# Stepper_Driver.net
KiCad netlist of a schematic drawn in EAGLE
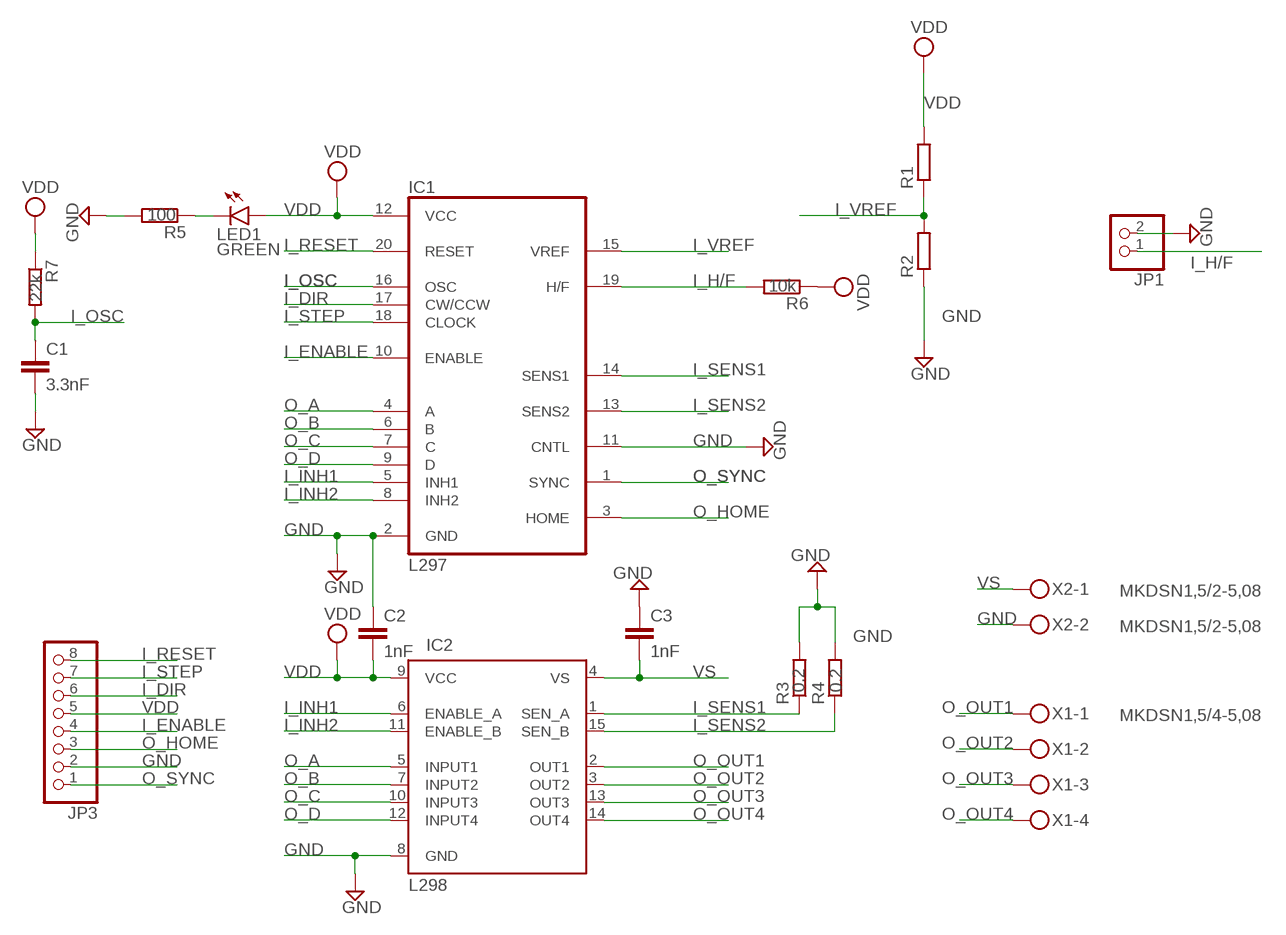
[diagram p0: schematic, sheet 1]

(export (version "E")
  (design (tool "Eeschema 10.0.6"))
  (components
    (comp (ref "C1")
      (value "3.3nF")
      (footprint "eagle-import:C0805K")
      (libsource (lib "eagle-import") (part "C-EUC0805K"))
    )
    (comp (ref "C2")
      (value "1nF")
      (footprint "eagle-import:C0805K")
      (libsource (lib "eagle-import") (part "C-EUC0805K"))
    )
    (comp (ref "C3")
      (value "1nF")
      (footprint "eagle-import:C0805K")
      (libsource (lib "eagle-import") (part "C-EUC0805K"))
    )
    (comp (ref "IC1")
      (value "L297")
      (footprint "eagle-import:DIL20")
      (fields (field (name "MPN") "L297/1"))
      (libsource (lib "eagle-import") (part "L297"))
    )
    (comp (ref "IC2")
      (value "L298")
      (footprint "eagle-import:MULTIWATT-15")
      (fields (field (name "MPN") "L298N"))
      (libsource (lib "eagle-import") (part "L298"))
    )
    (comp (ref "JP1")
      (value "PINHD-1X2")
      (footprint "eagle-import:1X02")
      (libsource (lib "eagle-import") (part "PINHD-1X2"))
    )
    (comp (ref "JP3")
      (value "PINHD-1X8")
      (footprint "eagle-import:1X08")
      (libsource (lib "eagle-import") (part "PINHD-1X8"))
    )
    (comp (ref "LED1")
      (value "GREEN")
      (footprint "eagle-import:LED5MM")
      (libsource (lib "eagle-import") (part "LED5MM"))
    )
    (comp (ref "R1")
      (value "R-EU_R0805")
      (footprint "eagle-import:R0805")
      (libsource (lib "eagle-import") (part "R-EU_R0805"))
    )
    (comp (ref "R2")
      (value "R-EU_R0805")
      (footprint "eagle-import:R0805")
      (libsource (lib "eagle-import") (part "R-EU_R0805"))
    )
    (comp (ref "R3")
      (value "0.2")
      (footprint "eagle-import:R2512")
      (libsource (lib "eagle-import") (part "R-EU_R2512"))
    )
    (comp (ref "R4")
      (value "0.2")
      (footprint "eagle-import:R2512")
      (libsource (lib "eagle-import") (part "R-EU_R2512"))
    )
    (comp (ref "R5")
      (value "100")
      (footprint "eagle-import:R0805")
      (libsource (lib "eagle-import") (part "R-EU_R0805"))
    )
    (comp (ref "R6")
      (value "10k")
      (footprint "eagle-import:R0805")
      (libsource (lib "eagle-import") (part "R-EU_R0805"))
    )
    (comp (ref "R7")
      (value "22k")
      (footprint "eagle-import:R0805")
      (libsource (lib "eagle-import") (part "R-EU_R0805"))
    )
    (comp (ref "X1")
      (value "MKDSN1,5/4-5,08")
      (footprint "eagle-import:MKDSN1,5_4-5,08")
      (libsource (lib "eagle-import") (part "MKDSN1,5/4-5,08"))
    )
    (comp (ref "X2")
      (value "MKDSN1,5/2-5,08")
      (footprint "eagle-import:MKDSN1,5_2-5,08")
      (libsource (lib "eagle-import") (part "MKDSN1,5/2-5,08"))
    )
  )
  (nets
    (net (code "1") (name "/I_DIR") (class "Default")
      (node (ref "IC1") (pin "17") (pinfunction "CW/CCW_17") (pintype "input"))
      (node (ref "JP3") (pin "6") (pinfunction "6_6") (pintype "passive"))
    )
    (net (code "2") (name "/I_ENABLE") (class "Default")
      (node (ref "IC1") (pin "10") (pinfunction "ENABLE_10") (pintype "input"))
      (node (ref "JP3") (pin "4") (pinfunction "4_4") (pintype "passive"))
    )
    (net (code "3") (name "/I_H{slash}F") (class "Default")
      (node (ref "IC1") (pin "19") (pinfunction "H/F_19") (pintype "input"))
      (node (ref "JP1") (pin "1") (pinfunction "1_1") (pintype "passive"))
      (node (ref "R6") (pin "2") (pinfunction "2_2") (pintype "passive"))
    )
    (net (code "4") (name "/I_INH1") (class "Default")
      (node (ref "IC1") (pin "5") (pinfunction "INH1_5") (pintype "output"))
      (node (ref "IC2") (pin "6") (pinfunction "ENABLE_A_6") (pintype "input"))
    )
    (net (code "5") (name "/I_INH2") (class "Default")
      (node (ref "IC1") (pin "8") (pinfunction "INH2_8") (pintype "output"))
      (node (ref "IC2") (pin "11") (pinfunction "ENABLE_B_11") (pintype "input"))
    )
    (net (code "6") (name "/I_OSC") (class "Default")
      (node (ref "C1") (pin "1") (pinfunction "1_1") (pintype "passive"))
      (node (ref "IC1") (pin "16") (pinfunction "OSC_16") (pintype "bidirectional"))
      (node (ref "R7") (pin "2") (pinfunction "2_2") (pintype "passive"))
    )
    (net (code "7") (name "/I_RESET") (class "Default")
      (node (ref "IC1") (pin "20") (pinfunction "RESET_20") (pintype "input"))
      (node (ref "JP3") (pin "8") (pinfunction "8_8") (pintype "passive"))
    )
    (net (code "8") (name "/I_SENS1") (class "Default")
      (node (ref "IC1") (pin "14") (pinfunction "SENS1_14") (pintype "output"))
      (node (ref "IC2") (pin "1") (pinfunction "SEN_A_1") (pintype "input"))
      (node (ref "R3") (pin "1") (pinfunction "1_1") (pintype "passive"))
    )
    (net (code "9") (name "/I_SENS2") (class "Default")
      (node (ref "IC1") (pin "13") (pinfunction "SENS2_13") (pintype "output"))
      (node (ref "IC2") (pin "15") (pinfunction "SEN_B_15") (pintype "input"))
      (node (ref "R4") (pin "1") (pinfunction "1_1") (pintype "passive"))
    )
    (net (code "10") (name "/I_STEP") (class "Default")
      (node (ref "IC1") (pin "18") (pinfunction "CLOCK_18") (pintype "input"))
      (node (ref "JP3") (pin "7") (pinfunction "7_7") (pintype "passive"))
    )
    (net (code "11") (name "/I_VREF") (class "Default")
      (node (ref "IC1") (pin "15") (pinfunction "VREF_15") (pintype "input"))
      (node (ref "R1") (pin "1") (pinfunction "1_1") (pintype "passive"))
      (node (ref "R2") (pin "2") (pinfunction "2_2") (pintype "passive"))
    )
    (net (code "12") (name "/O_A") (class "Default")
      (node (ref "IC1") (pin "4") (pinfunction "A_4") (pintype "output"))
      (node (ref "IC2") (pin "5") (pinfunction "INPUT1_5") (pintype "input"))
    )
    (net (code "13") (name "/O_B") (class "Default")
      (node (ref "IC1") (pin "6") (pinfunction "B_6") (pintype "output"))
      (node (ref "IC2") (pin "7") (pinfunction "INPUT2_7") (pintype "input"))
    )
    (net (code "14") (name "/O_C") (class "Default")
      (node (ref "IC1") (pin "7") (pinfunction "C_7") (pintype "output"))
      (node (ref "IC2") (pin "10") (pinfunction "INPUT3_10") (pintype "input"))
    )
    (net (code "15") (name "/O_D") (class "Default")
      (node (ref "IC1") (pin "9") (pinfunction "D_9") (pintype "output"))
      (node (ref "IC2") (pin "12") (pinfunction "INPUT4_12") (pintype "input"))
    )
    (net (code "16") (name "/O_HOME") (class "Default")
      (node (ref "IC1") (pin "3") (pinfunction "HOME_3") (pintype "output"))
      (node (ref "JP3") (pin "3") (pinfunction "3_3") (pintype "passive"))
    )
    (net (code "17") (name "/O_OUT1") (class "Default")
      (node (ref "IC2") (pin "2") (pinfunction "OUT1_2") (pintype "output"))
      (node (ref "X1") (pin "1") (pinfunction "KL_1") (pintype "passive"))
    )
    (net (code "18") (name "/O_OUT2") (class "Default")
      (node (ref "IC2") (pin "3") (pinfunction "OUT2_3") (pintype "output"))
      (node (ref "X1") (pin "2") (pinfunction "KL_2") (pintype "passive"))
    )
    (net (code "19") (name "/O_OUT3") (class "Default")
      (node (ref "IC2") (pin "13") (pinfunction "OUT3_13") (pintype "output"))
      (node (ref "X1") (pin "3") (pinfunction "KL_3") (pintype "passive"))
    )
    (net (code "20") (name "/O_OUT4") (class "Default")
      (node (ref "IC2") (pin "14") (pinfunction "OUT4_14") (pintype "output"))
      (node (ref "X1") (pin "4") (pinfunction "KL_4") (pintype "passive"))
    )
    (net (code "21") (name "/O_SYNC") (class "Default")
      (node (ref "IC1") (pin "1") (pinfunction "SYNC_1") (pintype "output"))
      (node (ref "JP3") (pin "1") (pinfunction "1_1") (pintype "passive"))
    )
    (net (code "22") (name "/VS") (class "Default")
      (node (ref "C3") (pin "2") (pinfunction "2_2") (pintype "passive"))
      (node (ref "IC2") (pin "4") (pinfunction "VS_4") (pintype "power_in"))
      (node (ref "X2") (pin "1") (pinfunction "KL_1") (pintype "passive"))
    )
    (net (code "23") (name "GND") (class "Default")
      (node (ref "C1") (pin "2") (pinfunction "2_2") (pintype "passive"))
      (node (ref "C2") (pin "1") (pinfunction "1_1") (pintype "passive"))
      (node (ref "C3") (pin "1") (pinfunction "1_1") (pintype "passive"))
      (node (ref "IC1") (pin "11") (pinfunction "CNTL_11") (pintype "input"))
      (node (ref "IC1") (pin "2") (pinfunction "GND_2") (pintype "power_in"))
      (node (ref "IC2") (pin "8") (pinfunction "GND_8") (pintype "power_in"))
      (node (ref "JP1") (pin "2") (pinfunction "2_2") (pintype "passive"))
      (node (ref "JP3") (pin "2") (pinfunction "2_2") (pintype "passive"))
      (node (ref "R2") (pin "1") (pinfunction "1_1") (pintype "passive"))
      (node (ref "R3") (pin "2") (pinfunction "2_2") (pintype "passive"))
      (node (ref "R4") (pin "2") (pinfunction "2_2") (pintype "passive"))
      (node (ref "R5") (pin "2") (pinfunction "2_2") (pintype "passive"))
      (node (ref "X2") (pin "2") (pinfunction "KL_2") (pintype "passive"))
    )
    (net (code "24") (name "Net-(LED1-C)") (class "Default")
      (node (ref "LED1") (pin "K") (pinfunction "C_K") (pintype "passive"))
      (node (ref "R5") (pin "1") (pinfunction "1_1") (pintype "passive"))
    )
    (net (code "25") (name "VDD") (class "Default")
      (node (ref "C2") (pin "2") (pinfunction "2_2") (pintype "passive"))
      (node (ref "IC1") (pin "12") (pinfunction "VCC_12") (pintype "power_in"))
      (node (ref "IC2") (pin "9") (pinfunction "VCC_9") (pintype "power_in"))
      (node (ref "JP3") (pin "5") (pinfunction "5_5") (pintype "passive"))
      (node (ref "LED1") (pin "A") (pinfunction "A_A") (pintype "passive"))
      (node (ref "R1") (pin "2") (pinfunction "2_2") (pintype "passive"))
      (node (ref "R6") (pin "1") (pinfunction "1_1") (pintype "passive"))
      (node (ref "R7") (pin "1") (pinfunction "1_1") (pintype "passive"))
    )
  )
)
